# CATS-EUROC-Radio.net
KiCad netlist of a schematic drawn in Altium Designer
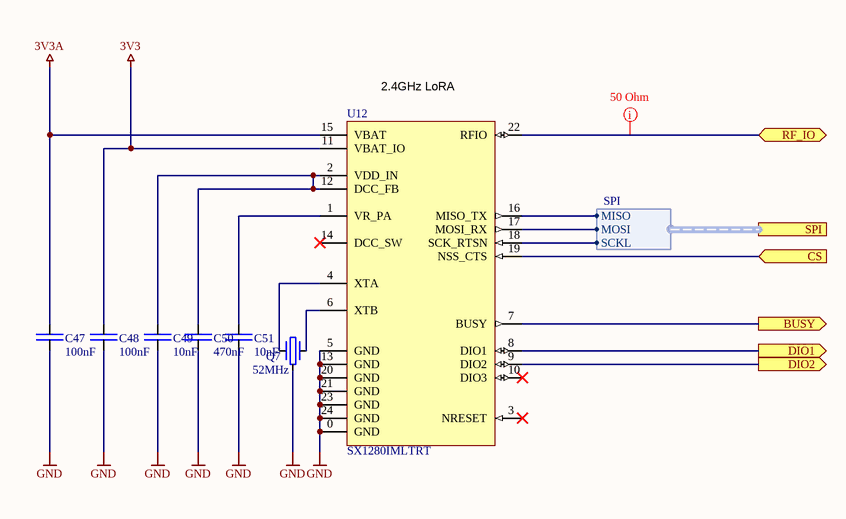
[diagram p0: CATS-EUROC-Radio.SchDoc]

(export (version "E")
  (design (tool "Eeschema 10.0.6"))
  (components
    (comp (ref "C47")
      (value "100nF")
      (footprint "SMD Keramikkondensator 0402")
      (description "SMD Ceramic Capacitor E6")
      (libsource (lib "CATS-EUROC") (part "E6 - 100nF"))
    )
    (comp (ref "C48")
      (value "100nF")
      (footprint "SMD Keramikkondensator 0402")
      (description "SMD Ceramic Capacitor E6")
      (libsource (lib "CATS-EUROC") (part "E6 - 100nF"))
    )
    (comp (ref "C49")
      (value "10nF")
      (footprint "SMD Keramikkondensator 0402")
      (description "SMD Ceramic Capacitor E6")
      (libsource (lib "CATS-EUROC") (part "E6 - 10nF"))
    )
    (comp (ref "C50")
      (value "470nF")
      (footprint "SMD Keramikkondensator 0402")
      (description "SMD Ceramic Capacitor E6")
      (libsource (lib "CATS-EUROC") (part "E6 - 470nF"))
    )
    (comp (ref "C51")
      (value "10nF")
      (footprint "SMD Keramikkondensator 0402")
      (description "SMD Ceramic Capacitor E6")
      (libsource (lib "CATS-EUROC") (part "E6 - 10nF"))
    )
    (comp (ref "Q7")
      (value "52MHz")
      (footprint "SMD Crystal 1.2X1.0X0.35")
      (description "52 MHz ±7ppm Crystal 5pF 100 Ohms 4-SMD, No Lead")
      (libsource (lib "Other") (part "Crystal 52MHz - R1210"))
    )
    (comp (ref "U12")
      (value "SX1280IMLTRT")
      (footprint "SMD IC QFN-24")
      (description "Long Range, Low Power, 2.4 GHz\r\nTransceiver with Ranging Capability")
      (libsource (lib "RF") (part "SX1280IMLTRT"))
    )
  )
  (nets
    (net (code "2") (name "/BUSY") (class "Default")
      (node (ref "U12") (pin "7") (pinfunction "BUSY_7") (pintype "output"))
    )
    (net (code "3") (name "/CS") (class "Default")
      (node (ref "U12") (pin "19") (pinfunction "NSS_CTS_19") (pintype "input"))
    )
    (net (code "4") (name "/DIO1") (class "Default")
      (node (ref "U12") (pin "8") (pinfunction "DIO1_8") (pintype "bidirectional"))
    )
    (net (code "5") (name "/DIO2") (class "Default")
      (node (ref "U12") (pin "9") (pinfunction "DIO2_9") (pintype "bidirectional"))
    )
    (net (code "6") (name "/MISO") (class "Default")
      (node (ref "U12") (pin "16") (pinfunction "MISO_TX_16") (pintype "output"))
    )
    (net (code "7") (name "/MOSI") (class "Default")
      (node (ref "U12") (pin "17") (pinfunction "MOSI_RX_17") (pintype "output"))
    )
    (net (code "8") (name "/RF_IO") (class "Default")
      (node (ref "U12") (pin "22") (pinfunction "RFIO_22") (pintype "bidirectional"))
    )
    (net (code "9") (name "/SCKL") (class "Default")
      (node (ref "U12") (pin "18") (pinfunction "SCK_RTSN_18") (pintype "input"))
    )
    (net (code "11") (name "3V3") (class "Default")
      (node (ref "C48") (pin "2") (pinfunction "2_2") (pintype "passive"))
      (node (ref "U12") (pin "11") (pinfunction "VBAT_IO_11") (pintype "passive"))
    )
    (net (code "12") (name "3V3A") (class "Default")
      (node (ref "C47") (pin "2") (pinfunction "2_2") (pintype "passive"))
      (node (ref "U12") (pin "15") (pinfunction "VBAT_15") (pintype "passive"))
    )
    (net (code "13") (name "GND") (class "Default")
      (node (ref "C47") (pin "1") (pinfunction "1_1") (pintype "passive"))
      (node (ref "C48") (pin "1") (pinfunction "1_1") (pintype "passive"))
      (node (ref "C49") (pin "1") (pinfunction "1_1") (pintype "passive"))
      (node (ref "C50") (pin "1") (pinfunction "1_1") (pintype "passive"))
      (node (ref "C51") (pin "1") (pinfunction "1_1") (pintype "passive"))
      (node (ref "Q7") (pin "3") (pinfunction "3_3") (pintype "power_in"))
      (node (ref "U12") (pin "0") (pinfunction "GND_0") (pintype "passive"))
      (node (ref "U12") (pin "13") (pinfunction "GND_13") (pintype "passive"))
      (node (ref "U12") (pin "20") (pinfunction "GND_20") (pintype "passive"))
      (node (ref "U12") (pin "21") (pinfunction "GND_21") (pintype "passive"))
      (node (ref "U12") (pin "23") (pinfunction "GND_23") (pintype "passive"))
      (node (ref "U12") (pin "24") (pinfunction "GND_24") (pintype "passive"))
      (node (ref "U12") (pin "5") (pinfunction "GND_5") (pintype "passive"))
    )
    (net (code "14") (name "Net-(U12-DCC_FB)") (class "Default")
      (node (ref "C49") (pin "2") (pinfunction "2_2") (pintype "passive"))
      (node (ref "C50") (pin "2") (pinfunction "2_2") (pintype "passive"))
      (node (ref "U12") (pin "12") (pinfunction "DCC_FB_12") (pintype "passive"))
      (node (ref "U12") (pin "2") (pinfunction "VDD_IN_2") (pintype "passive"))
    )
    (net (code "15") (name "Net-(U12-VR_PA)") (class "Default")
      (node (ref "C51") (pin "2") (pinfunction "2_2") (pintype "passive"))
      (node (ref "U12") (pin "1") (pinfunction "VR_PA_1") (pintype "passive"))
    )
    (net (code "16") (name "Net-(U12-XTA)") (class "Default")
      (node (ref "Q7") (pin "1") (pinfunction "1_1") (pintype "passive"))
      (node (ref "U12") (pin "4") (pinfunction "XTA_4") (pintype "passive"))
    )
    (net (code "17") (name "Net-(U12-XTB)") (class "Default")
      (node (ref "Q7") (pin "2") (pinfunction "2_2") (pintype "passive"))
      (node (ref "U12") (pin "6") (pinfunction "XTB_6") (pintype "passive"))
    )
    (net (code "18") (name "unconnected-(U12-DCC_SW-Pad14)") (class "Default")
      (node (ref "U12") (pin "14") (pinfunction "DCC_SW_14") (pintype "passive+no_connect"))
    )
    (net (code "19") (name "unconnected-(U12-DIO3-Pad10)") (class "Default")
      (node (ref "U12") (pin "10") (pinfunction "DIO3_10") (pintype "bidirectional+no_connect"))
    )
    (net (code "20") (name "unconnected-(U12-NRESET-Pad3)") (class "Default")
      (node (ref "U12") (pin "3") (pinfunction "NRESET_3") (pintype "input+no_connect"))
    )
  )
)
